# fita_LED.net
KiCad netlist of a schematic drawn in EAGLE
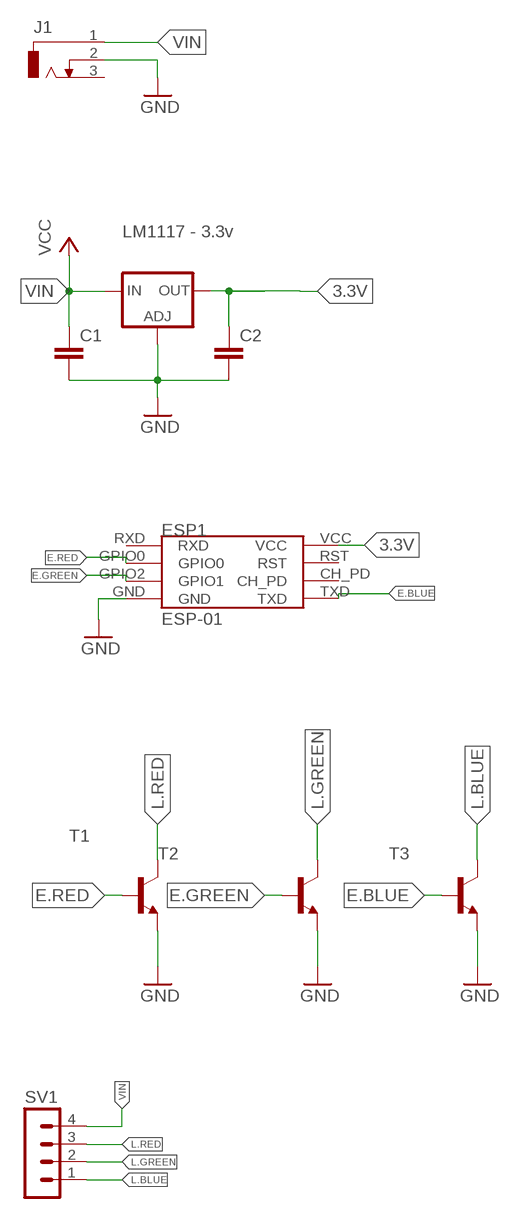
[diagram p0: schematic, sheet 1]

(export (version "E")
  (design (tool "Eeschema 10.0.6"))
  (components
    (comp (ref "C1")
      (value "C-EUC0805")
      (footprint "eagle-import:C0805")
      (libsource (lib "eagle-import") (part "C-EUC0805"))
    )
    (comp (ref "C2")
      (value "C-EUC0805")
      (footprint "eagle-import:C0805")
      (libsource (lib "eagle-import") (part "C-EUC0805"))
    )
    (comp (ref "ESP1")
      (value "ESP-01")
      (footprint "eagle-import:ESP-01")
      (fields (field (name "MF") "AI-Thinker"))
      (libsource (lib "eagle-import") (part "ESP-01"))
    )
    (comp (ref "IC1")
      (value "LM1117 - 3.3v")
      (footprint "eagle-import:SOT223")
      (libsource (lib "eagle-import") (part "LD117A?S18TR"))
    )
    (comp (ref "J1")
      (value "DCJ0303")
      (footprint "eagle-import:DCJ0303")
      (libsource (lib "eagle-import") (part "DCJ0303"))
    )
    (comp (ref "SV1")
      (value "MA04-1")
      (footprint "eagle-import:MA04-1")
      (libsource (lib "eagle-import") (part "MA04-1"))
    )
    (comp (ref "T1")
      (value "BC817-16-NPN-SOT23-BEC")
      (footprint "eagle-import:SOT23-BEC")
      (libsource (lib "eagle-import") (part "-NPN-SOT23-BECBC817-16"))
    )
    (comp (ref "T2")
      (value "BC817-16-NPN-SOT23-BEC")
      (footprint "eagle-import:SOT23-BEC")
      (libsource (lib "eagle-import") (part "-NPN-SOT23-BECBC817-16"))
    )
    (comp (ref "T3")
      (value "BC817-16-NPN-SOT23-BEC")
      (footprint "eagle-import:SOT23-BEC")
      (libsource (lib "eagle-import") (part "-NPN-SOT23-BECBC817-16"))
    )
  )
  (nets
    (net (code "1") (name "3.3V") (class "Default")
      (node (ref "C2") (pin "1") (pinfunction "1_1") (pintype "passive"))
      (node (ref "ESP1") (pin "VCC") (pinfunction "VCC_VCC") (pintype "bidirectional"))
      (node (ref "IC1") (pin "4") (pinfunction "OUT_4") (pintype "passive"))
    )
    (net (code "2") (name "E.BLUE") (class "Default")
      (node (ref "ESP1") (pin "TXD") (pinfunction "TXD_TXD") (pintype "bidirectional"))
      (node (ref "T3") (pin "B") (pinfunction "B_B") (pintype "passive"))
    )
    (net (code "3") (name "E.GREEN") (class "Default")
      (node (ref "ESP1") (pin "GPIO2") (pinfunction "GPIO1_GPIO2") (pintype "bidirectional"))
      (node (ref "T2") (pin "B") (pinfunction "B_B") (pintype "passive"))
    )
    (net (code "4") (name "E.RED") (class "Default")
      (node (ref "ESP1") (pin "GPIO0") (pinfunction "GPIO0_GPIO0") (pintype "bidirectional"))
      (node (ref "T1") (pin "B") (pinfunction "B_B") (pintype "passive"))
    )
    (net (code "5") (name "GND") (class "Default")
      (node (ref "C1") (pin "2") (pinfunction "2_2") (pintype "passive"))
      (node (ref "C2") (pin "2") (pinfunction "2_2") (pintype "passive"))
      (node (ref "ESP1") (pin "GND") (pinfunction "GND_GND") (pintype "bidirectional"))
      (node (ref "IC1") (pin "1") (pinfunction "ADJ_1") (pintype "input"))
      (node (ref "J1") (pin "2") (pinfunction "2_2") (pintype "passive"))
      (node (ref "T1") (pin "E") (pinfunction "E_E") (pintype "passive"))
      (node (ref "T2") (pin "E") (pinfunction "E_E") (pintype "passive"))
      (node (ref "T3") (pin "E") (pinfunction "E_E") (pintype "passive"))
    )
    (net (code "6") (name "L.BLUE") (class "Default")
      (node (ref "SV1") (pin "1") (pinfunction "1_1") (pintype "passive"))
      (node (ref "T3") (pin "C") (pinfunction "C_C") (pintype "passive"))
    )
    (net (code "7") (name "L.GREEN") (class "Default")
      (node (ref "SV1") (pin "2") (pinfunction "2_2") (pintype "passive"))
      (node (ref "T2") (pin "C") (pinfunction "C_C") (pintype "passive"))
    )
    (net (code "8") (name "L.RED") (class "Default")
      (node (ref "SV1") (pin "3") (pinfunction "3_3") (pintype "passive"))
      (node (ref "T1") (pin "C") (pinfunction "C_C") (pintype "passive"))
    )
    (net (code "9") (name "VIN") (class "Default")
      (node (ref "C1") (pin "1") (pinfunction "1_1") (pintype "passive"))
      (node (ref "IC1") (pin "3") (pinfunction "IN_3") (pintype "input"))
      (node (ref "J1") (pin "1") (pinfunction "1_1") (pintype "passive"))
      (node (ref "SV1") (pin "4") (pinfunction "4_4") (pintype "passive"))
    )
    (net (code "10") (name "unconnected-(ESP1-PadCH_PD)") (class "Default")
      (node (ref "ESP1") (pin "CH_PD") (pinfunction "CH_PD_CH_PD") (pintype "bidirectional"))
    )
    (net (code "11") (name "unconnected-(ESP1-PadRST)") (class "Default")
      (node (ref "ESP1") (pin "RST") (pinfunction "RST_RST") (pintype "bidirectional"))
    )
    (net (code "12") (name "unconnected-(ESP1-PadRXD)") (class "Default")
      (node (ref "ESP1") (pin "RXD") (pinfunction "RXD_RXD") (pintype "bidirectional"))
    )
    (net (code "13") (name "unconnected-(J1-Pad3)") (class "Default")
      (node (ref "J1") (pin "3") (pinfunction "3_3") (pintype "passive"))
    )
  )
)
